# univ_3-2-2-x-rev2.net
KiCad netlist of a schematic drawn in EAGLE
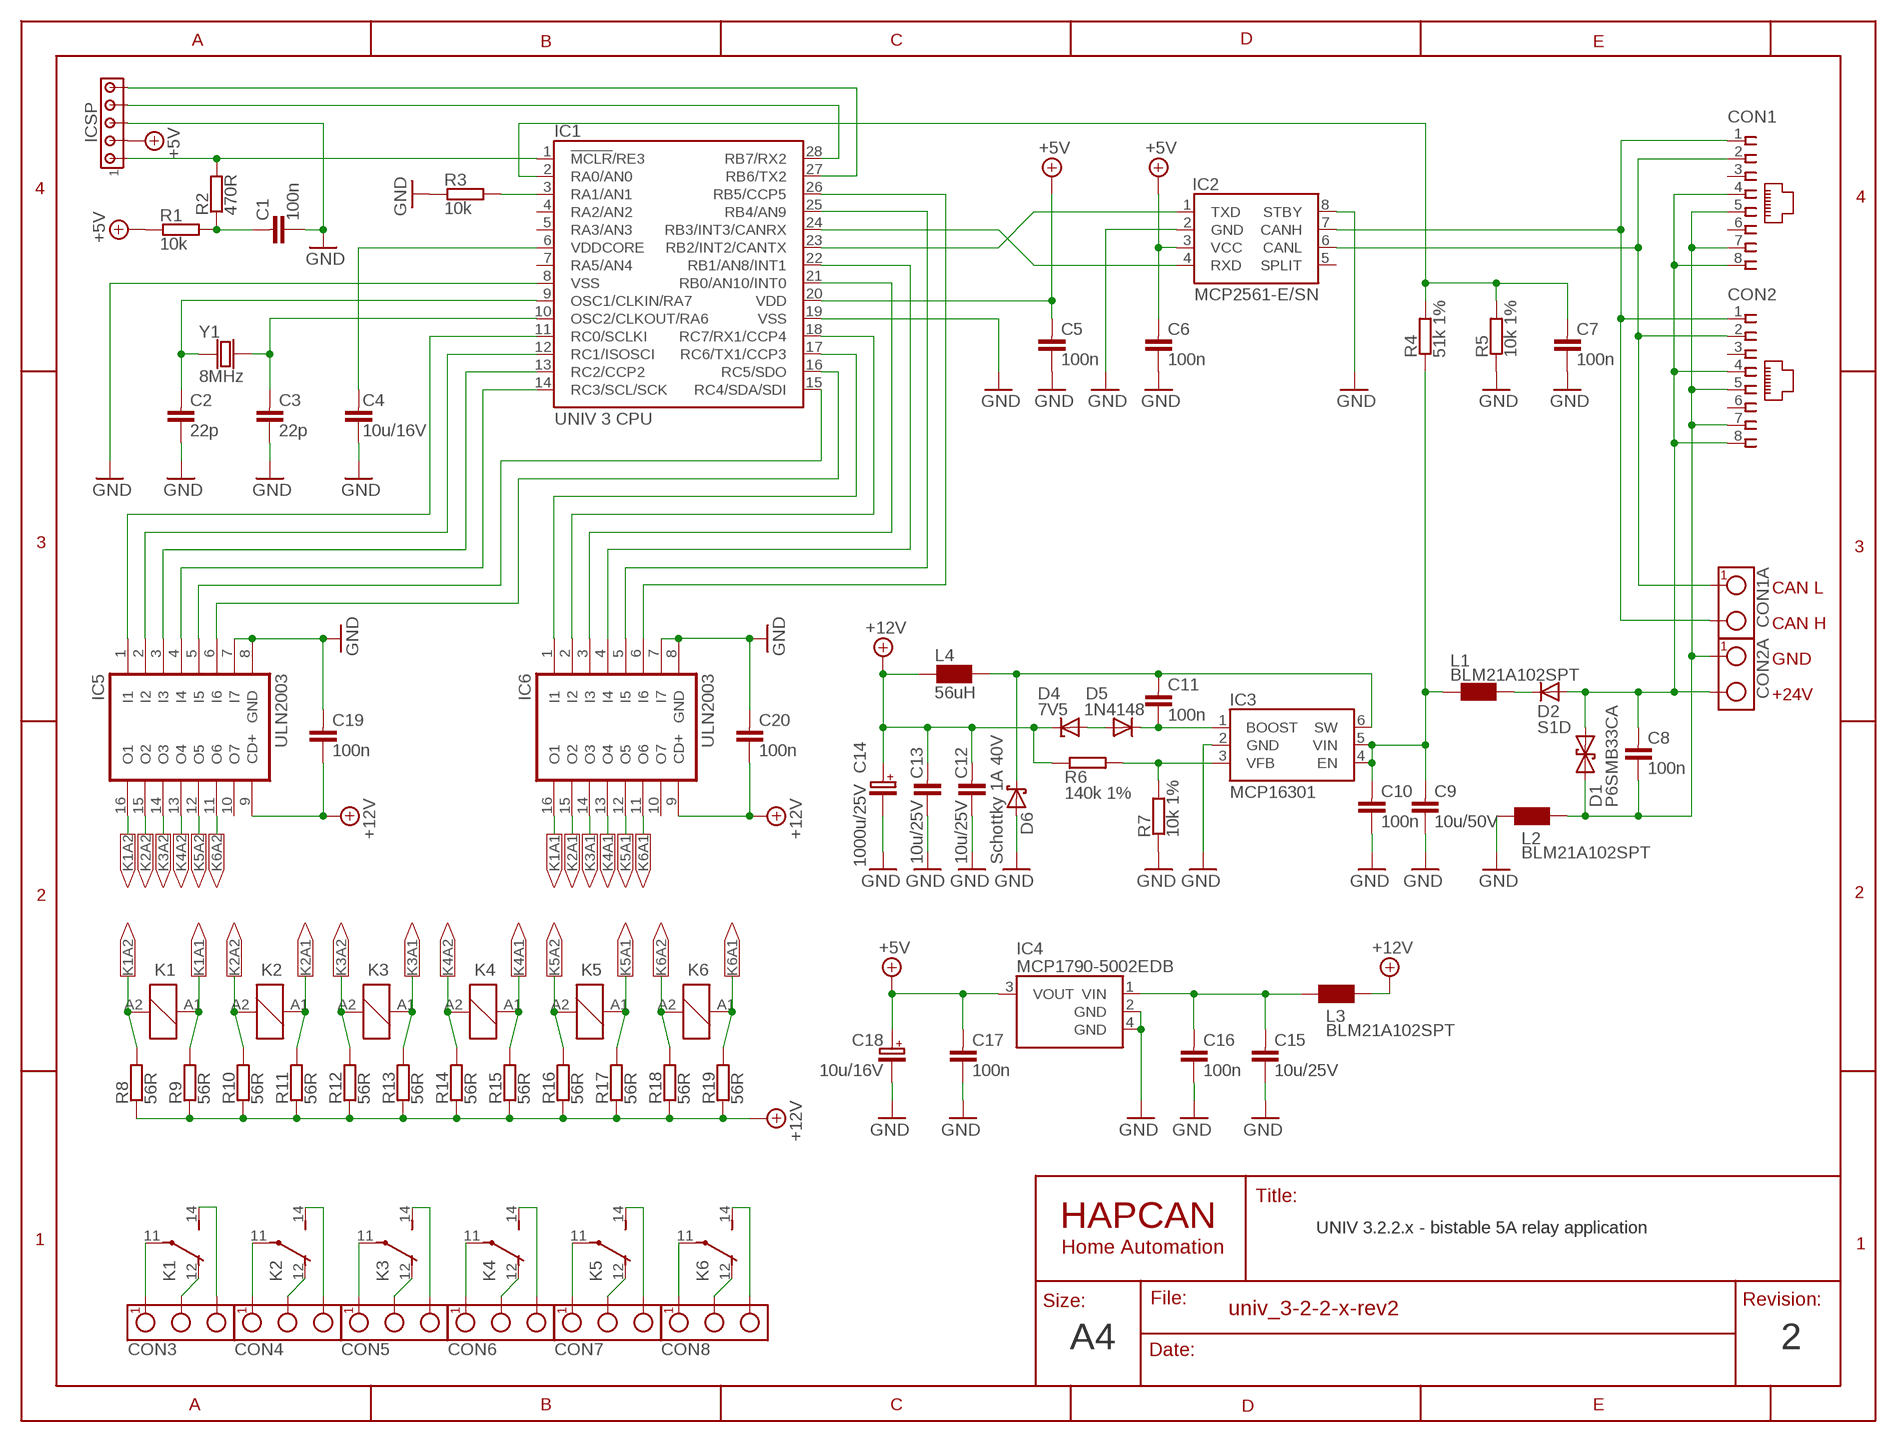
[diagram p0: schematic, sheet 1]

(export (version "E")
  (design (tool "Eeschema 10.0.6"))
  (components
    (comp (ref "C1")
      (value "100n")
      (footprint "eagle-import:0805")
      (libsource (lib "eagle-import") (part "CAPACITOR0805"))
    )
    (comp (ref "C2")
      (value "22p")
      (footprint "eagle-import:0805")
      (libsource (lib "eagle-import") (part "CAPACITOR0805"))
    )
    (comp (ref "C3")
      (value "22p")
      (footprint "eagle-import:0805")
      (libsource (lib "eagle-import") (part "CAPACITOR0805"))
    )
    (comp (ref "C4")
      (value "10u/16V")
      (footprint "eagle-import:0805")
      (libsource (lib "eagle-import") (part "CAPACITOR0805"))
    )
    (comp (ref "C5")
      (value "100n")
      (footprint "eagle-import:0805")
      (libsource (lib "eagle-import") (part "CAPACITOR0805"))
    )
    (comp (ref "C6")
      (value "100n")
      (footprint "eagle-import:0805")
      (libsource (lib "eagle-import") (part "CAPACITOR0805"))
    )
    (comp (ref "C7")
      (value "100n")
      (footprint "eagle-import:0805")
      (libsource (lib "eagle-import") (part "CAPACITOR0805"))
    )
    (comp (ref "C8")
      (value "100n")
      (footprint "eagle-import:0805")
      (libsource (lib "eagle-import") (part "CAPACITOR0805"))
    )
    (comp (ref "C9")
      (value "10u/50V")
      (footprint "eagle-import:1210")
      (libsource (lib "eagle-import") (part "CAPACITOR1210"))
    )
    (comp (ref "C10")
      (value "100n")
      (footprint "eagle-import:0805")
      (libsource (lib "eagle-import") (part "CAPACITOR0805"))
    )
    (comp (ref "C11")
      (value "100n")
      (footprint "eagle-import:0805")
      (libsource (lib "eagle-import") (part "CAPACITOR0805"))
    )
    (comp (ref "C12")
      (value "10u/25V")
      (footprint "eagle-import:1206")
      (libsource (lib "eagle-import") (part "CAPACITOR1206"))
    )
    (comp (ref "C13")
      (value "10u/25V")
      (footprint "eagle-import:1206")
      (libsource (lib "eagle-import") (part "CAPACITOR1206"))
    )
    (comp (ref "C14")
      (value "1000u/25V")
      (footprint "eagle-import:CAP-5X10.5")
      (libsource (lib "eagle-import") (part "CAPACITOR-POLARIZED-5X10.5"))
    )
    (comp (ref "C15")
      (value "10u/25V")
      (footprint "eagle-import:1206")
      (libsource (lib "eagle-import") (part "CAPACITOR1206"))
    )
    (comp (ref "C16")
      (value "100n")
      (footprint "eagle-import:0805")
      (libsource (lib "eagle-import") (part "CAPACITOR0805"))
    )
    (comp (ref "C17")
      (value "100n")
      (footprint "eagle-import:0805")
      (libsource (lib "eagle-import") (part "CAPACITOR0805"))
    )
    (comp (ref "C18")
      (value "10u/16V")
      (footprint "eagle-import:SMC_B")
      (libsource (lib "eagle-import") (part "CAPACITOR-POLARIZED-SMC_B"))
    )
    (comp (ref "C19")
      (value "100n")
      (footprint "eagle-import:0805")
      (libsource (lib "eagle-import") (part "CAPACITOR0805"))
    )
    (comp (ref "C20")
      (value "100n")
      (footprint "eagle-import:0805")
      (libsource (lib "eagle-import") (part "CAPACITOR0805"))
    )
    (comp (ref "CON1")
      (value "RJ45-SOCKET")
      (footprint "eagle-import:RJ45-PCB-SOCKET")
      (libsource (lib "eagle-import") (part "RJ45-SOCKET"))
    )
    (comp (ref "CON1A")
      (value "TERMINAL-2")
      (footprint "eagle-import:ARK2-5X10,5MM")
      (libsource (lib "eagle-import") (part "TERMINAL-2-5X10,5MM"))
    )
    (comp (ref "CON2")
      (value "RJ45-SOCKET")
      (footprint "eagle-import:RJ45-PCB-SOCKET")
      (libsource (lib "eagle-import") (part "RJ45-SOCKET"))
    )
    (comp (ref "CON2A")
      (value "TERMINAL-2")
      (footprint "eagle-import:ARK2-5X10,5MM")
      (libsource (lib "eagle-import") (part "TERMINAL-2-5X10,5MM"))
    )
    (comp (ref "CON3")
      (value "TERMINAL-3-5X10.5MM")
      (footprint "eagle-import:ARK3-5X10.5MM")
      (libsource (lib "eagle-import") (part "TERMINAL-3-5X10.5MM"))
    )
    (comp (ref "CON4")
      (value "TERMINAL-3-5X10.5MM")
      (footprint "eagle-import:ARK3-5X10.5MM")
      (libsource (lib "eagle-import") (part "TERMINAL-3-5X10.5MM"))
    )
    (comp (ref "CON5")
      (value "TERMINAL-3-5X10.5MM")
      (footprint "eagle-import:ARK3-5X10.5MM")
      (libsource (lib "eagle-import") (part "TERMINAL-3-5X10.5MM"))
    )
    (comp (ref "CON6")
      (value "TERMINAL-3-5X10.5MM")
      (footprint "eagle-import:ARK3-5X10.5MM")
      (libsource (lib "eagle-import") (part "TERMINAL-3-5X10.5MM"))
    )
    (comp (ref "CON7")
      (value "TERMINAL-3-5X10.5MM")
      (footprint "eagle-import:ARK3-5X10.5MM")
      (libsource (lib "eagle-import") (part "TERMINAL-3-5X10.5MM"))
    )
    (comp (ref "CON8")
      (value "TERMINAL-3-5X10.5MM")
      (footprint "eagle-import:ARK3-5X10.5MM")
      (libsource (lib "eagle-import") (part "TERMINAL-3-5X10.5MM"))
    )
    (comp (ref "D1")
      (value "P6SMB33CA")
      (footprint "eagle-import:DO-214_TRANSIL2")
      (libsource (lib "eagle-import") (part "DIODE_TRANSIL2"))
    )
    (comp (ref "D2")
      (value "S1D")
      (footprint "eagle-import:DO-214")
      (libsource (lib "eagle-import") (part "DIODE_DO-214"))
    )
    (comp (ref "D4")
      (value "7V5")
      (footprint "eagle-import:SOD-80")
      (libsource (lib "eagle-import") (part "DIODE_ZENER_SOD-80"))
    )
    (comp (ref "D5")
      (value "1N4148")
      (footprint "eagle-import:0805")
      (libsource (lib "eagle-import") (part "DIODE_0805"))
    )
    (comp (ref "D6")
      (value "Schottky 1A 40V")
      (footprint "eagle-import:DO-214")
      (libsource (lib "eagle-import") (part "DIODE_TRANSIL1_DO214"))
    )
    (comp (ref "IC1")
      (value "UNIV 3 CPU")
      (footprint "eagle-import:UNIV3CPU")
      (libsource (lib "eagle-import") (part "UNIV3CPU-I/SO"))
    )
    (comp (ref "IC2")
      (value "MCP2561-E/SN")
      (footprint "eagle-import:SO-08")
      (libsource (lib "eagle-import") (part "MCP2561-E/SN"))
    )
    (comp (ref "IC3")
      (value "MCP16301")
      (footprint "eagle-import:SOT-23-6")
      (libsource (lib "eagle-import") (part "MCP16301SOT23-6"))
    )
    (comp (ref "IC4")
      (value "MCP1790-5002EDB")
      (footprint "eagle-import:SOT-223")
      (libsource (lib "eagle-import") (part "MCP1826SOT223-3"))
    )
    (comp (ref "IC5")
      (value "ULN2003")
      (footprint "eagle-import:SO-16")
      (libsource (lib "eagle-import") (part "ULN2003"))
    )
    (comp (ref "IC6")
      (value "ULN2003")
      (footprint "eagle-import:SO-16")
      (libsource (lib "eagle-import") (part "ULN2003"))
    )
    (comp (ref "ICSP")
      (value "HEADER5")
      (footprint "eagle-import:SIP-5")
      (libsource (lib "eagle-import") (part "HEADER5"))
    )
    (comp (ref "K1")
      (value "RELAY_PE")
      (footprint "eagle-import:RELAY_PE")
      (libsource (lib "eagle-import") (part "RELAY_PE"))
    )
    (comp (ref "K2")
      (value "RELAY_PE")
      (footprint "eagle-import:RELAY_PE")
      (libsource (lib "eagle-import") (part "RELAY_PE"))
    )
    (comp (ref "K3")
      (value "RELAY_PE")
      (footprint "eagle-import:RELAY_PE")
      (libsource (lib "eagle-import") (part "RELAY_PE"))
    )
    (comp (ref "K4")
      (value "RELAY_PE")
      (footprint "eagle-import:RELAY_PE")
      (libsource (lib "eagle-import") (part "RELAY_PE"))
    )
    (comp (ref "K5")
      (value "RELAY_PE")
      (footprint "eagle-import:RELAY_PE")
      (libsource (lib "eagle-import") (part "RELAY_PE"))
    )
    (comp (ref "K6")
      (value "RELAY_PE")
      (footprint "eagle-import:RELAY_PE")
      (libsource (lib "eagle-import") (part "RELAY_PE"))
    )
    (comp (ref "L1")
      (value "BLM21A102SPT")
      (footprint "eagle-import:0805")
      (libsource (lib "eagle-import") (part "CHOKE0805"))
    )
    (comp (ref "L2")
      (value "BLM21A102SPT")
      (footprint "eagle-import:0805")
      (libsource (lib "eagle-import") (part "CHOKE0805"))
    )
    (comp (ref "L3")
      (value "BLM21A102SPT")
      (footprint "eagle-import:0805")
      (libsource (lib "eagle-import") (part "CHOKE0805"))
    )
    (comp (ref "L4")
      (value "56uH")
      (footprint "eagle-import:CHOKE-DER0705")
      (libsource (lib "eagle-import") (part "CHOKEDER0705"))
    )
    (comp (ref "R1")
      (value "10k")
      (footprint "eagle-import:0805")
      (libsource (lib "eagle-import") (part "RESISTOR0805"))
    )
    (comp (ref "R2")
      (value "470R")
      (footprint "eagle-import:0805")
      (libsource (lib "eagle-import") (part "RESISTOR0805"))
    )
    (comp (ref "R3")
      (value "10k")
      (footprint "eagle-import:0805")
      (libsource (lib "eagle-import") (part "RESISTOR0805"))
    )
    (comp (ref "R4")
      (value "51k 1%")
      (footprint "eagle-import:0805")
      (libsource (lib "eagle-import") (part "RESISTOR0805"))
    )
    (comp (ref "R5")
      (value "10k 1%")
      (footprint "eagle-import:0805")
      (libsource (lib "eagle-import") (part "RESISTOR0805"))
    )
    (comp (ref "R6")
      (value "140k 1%")
      (footprint "eagle-import:0805")
      (libsource (lib "eagle-import") (part "RESISTOR0805"))
    )
    (comp (ref "R7")
      (value "10k 1%")
      (footprint "eagle-import:0805")
      (libsource (lib "eagle-import") (part "RESISTOR0805"))
    )
    (comp (ref "R8")
      (value "56R")
      (footprint "eagle-import:1206")
      (libsource (lib "eagle-import") (part "RESISTOR1206"))
    )
    (comp (ref "R9")
      (value "56R")
      (footprint "eagle-import:1206")
      (libsource (lib "eagle-import") (part "RESISTOR1206"))
    )
    (comp (ref "R10")
      (value "56R")
      (footprint "eagle-import:1206")
      (libsource (lib "eagle-import") (part "RESISTOR1206"))
    )
    (comp (ref "R11")
      (value "56R")
      (footprint "eagle-import:1206")
      (libsource (lib "eagle-import") (part "RESISTOR1206"))
    )
    (comp (ref "R12")
      (value "56R")
      (footprint "eagle-import:1206")
      (libsource (lib "eagle-import") (part "RESISTOR1206"))
    )
    (comp (ref "R13")
      (value "56R")
      (footprint "eagle-import:1206")
      (libsource (lib "eagle-import") (part "RESISTOR1206"))
    )
    (comp (ref "R14")
      (value "56R")
      (footprint "eagle-import:1206")
      (libsource (lib "eagle-import") (part "RESISTOR1206"))
    )
    (comp (ref "R15")
      (value "56R")
      (footprint "eagle-import:1206")
      (libsource (lib "eagle-import") (part "RESISTOR1206"))
    )
    (comp (ref "R16")
      (value "56R")
      (footprint "eagle-import:1206")
      (libsource (lib "eagle-import") (part "RESISTOR1206"))
    )
    (comp (ref "R17")
      (value "56R")
      (footprint "eagle-import:1206")
      (libsource (lib "eagle-import") (part "RESISTOR1206"))
    )
    (comp (ref "R18")
      (value "56R")
      (footprint "eagle-import:1206")
      (libsource (lib "eagle-import") (part "RESISTOR1206"))
    )
    (comp (ref "R19")
      (value "56R")
      (footprint "eagle-import:1206")
      (libsource (lib "eagle-import") (part "RESISTOR1206"))
    )
    (comp (ref "Y1")
      (value "8MHz")
      (footprint "eagle-import:CRYSTAL-HC49V")
      (libsource (lib "eagle-import") (part "CRYSTAL-HC49V"))
    )
  )
  (nets
    (net (code "1") (name "+5V") (class "Default")
      (node (ref "C17") (pin "1") (pinfunction "1_1") (pintype "passive"))
      (node (ref "C18") (pin "+") (pinfunction "1_+") (pintype "passive"))
      (node (ref "C5") (pin "1") (pinfunction "1_1") (pintype "passive"))
      (node (ref "C6") (pin "1") (pinfunction "1_1") (pintype "passive"))
      (node (ref "IC1") (pin "20") (pinfunction "VDD_20") (pintype "bidirectional"))
      (node (ref "IC2") (pin "3") (pinfunction "VCC_3") (pintype "bidirectional"))
      (node (ref "IC4") (pin "3") (pinfunction "VOUT_3") (pintype "bidirectional"))
      (node (ref "ICSP") (pin "2") (pinfunction "2_2") (pintype "passive"))
      (node (ref "R1") (pin "1") (pinfunction "1_1") (pintype "passive"))
    )
    (net (code "2") (name "+12V") (class "Default")
      (node (ref "C12") (pin "1") (pinfunction "1_1") (pintype "passive"))
      (node (ref "C13") (pin "1") (pinfunction "1_1") (pintype "passive"))
      (node (ref "C14") (pin "+") (pinfunction "1_+") (pintype "passive"))
      (node (ref "C19") (pin "2") (pinfunction "2_2") (pintype "passive"))
      (node (ref "C20") (pin "2") (pinfunction "2_2") (pintype "passive"))
      (node (ref "D4") (pin "C") (pinfunction "C_C") (pintype "passive"))
      (node (ref "IC5") (pin "9") (pinfunction "CD+_9") (pintype "passive"))
      (node (ref "IC6") (pin "9") (pinfunction "CD+_9") (pintype "passive"))
      (node (ref "L3") (pin "2") (pinfunction "2_2") (pintype "passive"))
      (node (ref "L4") (pin "1") (pinfunction "1_1") (pintype "passive"))
      (node (ref "R10") (pin "1") (pinfunction "1_1") (pintype "passive"))
      (node (ref "R11") (pin "1") (pinfunction "1_1") (pintype "passive"))
      (node (ref "R12") (pin "1") (pinfunction "1_1") (pintype "passive"))
      (node (ref "R13") (pin "1") (pinfunction "1_1") (pintype "passive"))
      (node (ref "R14") (pin "1") (pinfunction "1_1") (pintype "passive"))
      (node (ref "R15") (pin "1") (pinfunction "1_1") (pintype "passive"))
      (node (ref "R16") (pin "1") (pinfunction "1_1") (pintype "passive"))
      (node (ref "R17") (pin "1") (pinfunction "1_1") (pintype "passive"))
      (node (ref "R18") (pin "1") (pinfunction "1_1") (pintype "passive"))
      (node (ref "R19") (pin "1") (pinfunction "1_1") (pintype "passive"))
      (node (ref "R6") (pin "1") (pinfunction "1_1") (pintype "passive"))
      (node (ref "R8") (pin "1") (pinfunction "1_1") (pintype "passive"))
      (node (ref "R9") (pin "1") (pinfunction "1_1") (pintype "passive"))
    )
    (net (code "3") (name "/K1A1") (class "Default")
      (node (ref "IC6") (pin "16") (pinfunction "O1_16") (pintype "open_collector"))
      (node (ref "K1") (pin "A1") (pinfunction "1_A1") (pintype "passive"))
      (node (ref "R9") (pin "2") (pinfunction "2_2") (pintype "passive"))
    )
    (net (code "4") (name "/K1A2") (class "Default")
      (node (ref "IC5") (pin "16") (pinfunction "O1_16") (pintype "open_collector"))
      (node (ref "K1") (pin "A2") (pinfunction "2_A2") (pintype "passive"))
      (node (ref "R8") (pin "2") (pinfunction "2_2") (pintype "passive"))
    )
    (net (code "5") (name "/K2A1") (class "Default")
      (node (ref "IC6") (pin "15") (pinfunction "O2_15") (pintype "open_collector"))
      (node (ref "K2") (pin "A1") (pinfunction "1_A1") (pintype "passive"))
      (node (ref "R11") (pin "2") (pinfunction "2_2") (pintype "passive"))
    )
    (net (code "6") (name "/K2A2") (class "Default")
      (node (ref "IC5") (pin "15") (pinfunction "O2_15") (pintype "open_collector"))
      (node (ref "K2") (pin "A2") (pinfunction "2_A2") (pintype "passive"))
      (node (ref "R10") (pin "2") (pinfunction "2_2") (pintype "passive"))
    )
    (net (code "7") (name "/K3A1") (class "Default")
      (node (ref "IC6") (pin "14") (pinfunction "O3_14") (pintype "open_collector"))
      (node (ref "K3") (pin "A1") (pinfunction "1_A1") (pintype "passive"))
      (node (ref "R13") (pin "2") (pinfunction "2_2") (pintype "passive"))
    )
    (net (code "8") (name "/K3A2") (class "Default")
      (node (ref "IC5") (pin "14") (pinfunction "O3_14") (pintype "open_collector"))
      (node (ref "K3") (pin "A2") (pinfunction "2_A2") (pintype "passive"))
      (node (ref "R12") (pin "2") (pinfunction "2_2") (pintype "passive"))
    )
    (net (code "9") (name "/K4A1") (class "Default")
      (node (ref "IC6") (pin "13") (pinfunction "O4_13") (pintype "open_collector"))
      (node (ref "K4") (pin "A1") (pinfunction "1_A1") (pintype "passive"))
      (node (ref "R15") (pin "2") (pinfunction "2_2") (pintype "passive"))
    )
    (net (code "10") (name "/K4A2") (class "Default")
      (node (ref "IC5") (pin "13") (pinfunction "O4_13") (pintype "open_collector"))
      (node (ref "K4") (pin "A2") (pinfunction "2_A2") (pintype "passive"))
      (node (ref "R14") (pin "2") (pinfunction "2_2") (pintype "passive"))
    )
    (net (code "11") (name "/K5A1") (class "Default")
      (node (ref "IC6") (pin "12") (pinfunction "O5_12") (pintype "open_collector"))
      (node (ref "K5") (pin "A1") (pinfunction "1_A1") (pintype "passive"))
      (node (ref "R17") (pin "2") (pinfunction "2_2") (pintype "passive"))
    )
    (net (code "12") (name "/K5A2") (class "Default")
      (node (ref "IC5") (pin "12") (pinfunction "O5_12") (pintype "open_collector"))
      (node (ref "K5") (pin "A2") (pinfunction "2_A2") (pintype "passive"))
      (node (ref "R16") (pin "2") (pinfunction "2_2") (pintype "passive"))
    )
    (net (code "13") (name "/K6A1") (class "Default")
      (node (ref "IC6") (pin "11") (pinfunction "O6_11") (pintype "open_collector"))
      (node (ref "K6") (pin "A1") (pinfunction "1_A1") (pintype "passive"))
      (node (ref "R19") (pin "2") (pinfunction "2_2") (pintype "passive"))
    )
    (net (code "14") (name "/K6A2") (class "Default")
      (node (ref "IC5") (pin "11") (pinfunction "O6_11") (pintype "open_collector"))
      (node (ref "K6") (pin "A2") (pinfunction "2_A2") (pintype "passive"))
      (node (ref "R18") (pin "2") (pinfunction "2_2") (pintype "passive"))
    )
    (net (code "15") (name "GND") (class "Default")
      (node (ref "C1") (pin "2") (pinfunction "2_2") (pintype "passive"))
      (node (ref "C10") (pin "2") (pinfunction "2_2") (pintype "passive"))
      (node (ref "C12") (pin "2") (pinfunction "2_2") (pintype "passive"))
      (node (ref "C13") (pin "2") (pinfunction "2_2") (pintype "passive"))
      (node (ref "C14") (pin "-") (pinfunction "2_-") (pintype "passive"))
      (node (ref "C15") (pin "2") (pinfunction "2_2") (pintype "passive"))
      (node (ref "C16") (pin "2") (pinfunction "2_2") (pintype "passive"))
      (node (ref "C17") (pin "2") (pinfunction "2_2") (pintype "passive"))
      (node (ref "C18") (pin "-") (pinfunction "2_-") (pintype "passive"))
      (node (ref "C19") (pin "1") (pinfunction "1_1") (pintype "passive"))
      (node (ref "C2") (pin "2") (pinfunction "2_2") (pintype "passive"))
      (node (ref "C20") (pin "1") (pinfunction "1_1") (pintype "passive"))
      (node (ref "C3") (pin "2") (pinfunction "2_2") (pintype "passive"))
      (node (ref "C4") (pin "2") (pinfunction "2_2") (pintype "passive"))
      (node (ref "C5") (pin "2") (pinfunction "2_2") (pintype "passive"))
      (node (ref "C6") (pin "2") (pinfunction "2_2") (pintype "passive"))
      (node (ref "C7") (pin "2") (pinfunction "2_2") (pintype "passive"))
      (node (ref "C9") (pin "2") (pinfunction "2_2") (pintype "passive"))
      (node (ref "D6") (pin "A") (pinfunction "A_A") (pintype "passive"))
      (node (ref "IC1") (pin "19") (pinfunction "VSS_19") (pintype "bidirectional"))
      (node (ref "IC1") (pin "8") (pinfunction "VSS_8") (pintype "bidirectional"))
      (node (ref "IC2") (pin "2") (pinfunction "GND_2") (pintype "bidirectional"))
      (node (ref "IC2") (pin "8") (pinfunction "STBY_8") (pintype "bidirectional"))
      (node (ref "IC3") (pin "2") (pinfunction "GND_2") (pintype "bidirectional"))
      (node (ref "IC4") (pin "2") (pinfunction "GND_2") (pintype "bidirectional"))
      (node (ref "IC4") (pin "4") (pinfunction "GND_4") (pintype "bidirectional"))
      (node (ref "IC5") (pin "7") (pinfunction "I7_7") (pintype "input"))
      (node (ref "IC5") (pin "8") (pinfunction "GND_8") (pintype "power_in"))
      (node (ref "IC6") (pin "7") (pinfunction "I7_7") (pintype "input"))
      (node (ref "IC6") (pin "8") (pinfunction "GND_8") (pintype "power_in"))
      (node (ref "ICSP") (pin "3") (pinfunction "3_3") (pintype "passive"))
      (node (ref "L2") (pin "1") (pinfunction "1_1") (pintype "passive"))
      (node (ref "R3") (pin "1") (pinfunction "1_1") (pintype "passive"))
      (node (ref "R5") (pin "1") (pinfunction "1_1") (pintype "passive"))
      (node (ref "R7") (pin "1") (pinfunction "1_1") (pintype "passive"))
    )
    (net (code "16") (name "Net-(C1-Pad1)") (class "Default")
      (node (ref "C1") (pin "1") (pinfunction "1_1") (pintype "passive"))
      (node (ref "R1") (pin "2") (pinfunction "2_2") (pintype "passive"))
      (node (ref "R2") (pin "1") (pinfunction "1_1") (pintype "passive"))
    )
    (net (code "17") (name "Net-(D1-1)") (class "Default")
      (node (ref "C8") (pin "2") (pinfunction "2_2") (pintype "passive"))
      (node (ref "CON1") (pin "5") (pinfunction "5_5") (pintype "passive"))
      (node (ref "CON1") (pin "7") (pinfunction "7_7") (pintype "passive"))
      (node (ref "CON2") (pin "5") (pinfunction "5_5") (pintype "passive"))
      (node (ref "CON2") (pin "7") (pinfunction "7_7") (pintype "passive"))
      (node (ref "CON2A") (pin "1") (pinfunction "1_1") (pintype "passive"))
      (node (ref "D1") (pin "A") (pinfunction "1_A") (pintype "passive"))
      (node (ref "L2") (pin "2") (pinfunction "2_2") (pintype "passive"))
    )
    (net (code "18") (name "Net-(D1-2)") (class "Default")
      (node (ref "C8") (pin "1") (pinfunction "1_1") (pintype "passive"))
      (node (ref "CON1") (pin "4") (pinfunction "4_4") (pintype "passive"))
      (node (ref "CON1") (pin "8") (pinfunction "8_8") (pintype "passive"))
      (node (ref "CON2") (pin "4") (pinfunction "4_4") (pintype "passive"))
      (node (ref "CON2") (pin "8") (pinfunction "8_8") (pintype "passive"))
      (node (ref "CON2A") (pin "2") (pinfunction "2_2") (pintype "passive"))
      (node (ref "D1") (pin "C") (pinfunction "2_C") (pintype "passive"))
      (node (ref "D2") (pin "A") (pinfunction "A_A") (pintype "passive"))
    )
    (net (code "19") (name "Net-(D2-PadC)") (class "Default")
      (node (ref "D2") (pin "C") (pinfunction "C_C") (pintype "passive"))
      (node (ref "L1") (pin "2") (pinfunction "2_2") (pintype "passive"))
    )
    (net (code "20") (name "Net-(D5-A)") (class "Default")
      (node (ref "D4") (pin "A") (pinfunction "A_A") (pintype "passive"))
      (node (ref "D5") (pin "2") (pinfunction "A_2") (pintype "passive"))
    )
    (net (code "21") (name "Net-(D5-C)") (class "Default")
      (node (ref "C11") (pin "2") (pinfunction "2_2") (pintype "passive"))
      (node (ref "D5") (pin "1") (pinfunction "C_1") (pintype "passive"))
      (node (ref "IC3") (pin "1") (pinfunction "BOOST_1") (pintype "bidirectional"))
    )
    (net (code "22") (name "Net-(IC1-OSC1{slash}CLKIN{slash}RA7)") (class "Default")
      (node (ref "C2") (pin "1") (pinfunction "1_1") (pintype "passive"))
      (node (ref "IC1") (pin "9") (pinfunction "OSC1/CLKIN/RA7_9") (pintype "bidirectional"))
      (node (ref "Y1") (pin "1") (pinfunction "1_1") (pintype "passive"))
    )
    (net (code "23") (name "Net-(IC1-OSC2{slash}CLKOUT{slash}RA6)") (class "Default")
      (node (ref "C3") (pin "1") (pinfunction "1_1") (pintype "passive"))
      (node (ref "IC1") (pin "10") (pinfunction "OSC2/CLKOUT/RA6_10") (pintype "bidirectional"))
      (node (ref "Y1") (pin "2") (pinfunction "2_2") (pintype "passive"))
    )
    (net (code "24") (name "Net-(IC1-RA0{slash}AN0)") (class "Default")
      (node (ref "C7") (pin "1") (pinfunction "1_1") (pintype "passive"))
      (node (ref "IC1") (pin "2") (pinfunction "RA0/AN0_2") (pintype "bidirectional"))
      (node (ref "R4") (pin "2") (pinfunction "2_2") (pintype "passive"))
      (node (ref "R5") (pin "2") (pinfunction "2_2") (pintype "passive"))
    )
    (net (code "25") (name "Net-(IC1-RA1{slash}AN1)") (class "Default")
      (node (ref "IC1") (pin "3") (pinfunction "RA1/AN1_3") (pintype "bidirectional"))
      (node (ref "R3") (pin "2") (pinfunction "2_2") (pintype "passive"))
    )
    (net (code "26") (name "Net-(IC1-RB0{slash}AN10{slash}INT0)") (class "Default")
      (node (ref "IC1") (pin "21") (pinfunction "RB0/AN10/INT0_21") (pintype "bidirectional"))
      (node (ref "IC6") (pin "3") (pinfunction "I3_3") (pintype "input"))
    )
    (net (code "27") (name "Net-(IC1-RB1{slash}AN8{slash}INT1)") (class "Default")
      (node (ref "IC1") (pin "22") (pinfunction "RB1/AN8/INT1_22") (pintype "bidirectional"))
      (node (ref "IC6") (pin "4") (pinfunction "I4_4") (pintype "input"))
    )
    (net (code "28") (name "Net-(IC1-RB2{slash}INT2{slash}CANTX)") (class "Default")
      (node (ref "IC1") (pin "23") (pinfunction "RB2/INT2/CANTX_23") (pintype "bidirectional"))
      (node (ref "IC2") (pin "1") (pinfunction "TXD_1") (pintype "bidirectional"))
    )
    (net (code "29") (name "Net-(IC1-RB3{slash}INT3{slash}CANRX)") (class "Default")
      (node (ref "IC1") (pin "24") (pinfunction "RB3/INT3/CANRX_24") (pintype "bidirectional"))
      (node (ref "IC2") (pin "4") (pinfunction "RXD_4") (pintype "bidirectional"))
    )
    (net (code "30") (name "Net-(IC1-RB4{slash}AN9)") (class "Default")
      (node (ref "IC1") (pin "25") (pinfunction "RB4/AN9_25") (pintype "bidirectional"))
      (node (ref "IC6") (pin "5") (pinfunction "I5_5") (pintype "input"))
    )
    (net (code "31") (name "Net-(IC1-RB5{slash}CCP5)") (class "Default")
      (node (ref "IC1") (pin "26") (pinfunction "RB5/CCP5_26") (pintype "bidirectional"))
      (node (ref "IC6") (pin "6") (pinfunction "I6_6") (pintype "input"))
    )
    (net (code "32") (name "Net-(IC1-RB6{slash}TX2)") (class "Default")
      (node (ref "IC1") (pin "27") (pinfunction "RB6/TX2_27") (pintype "bidirectional"))
      (node (ref "ICSP") (pin "5") (pinfunction "5_5") (pintype "passive"))
    )
    (net (code "33") (name "Net-(IC1-RB7{slash}RX2)") (class "Default")
      (node (ref "IC1") (pin "28") (pinfunction "RB7/RX2_28") (pintype "bidirectional"))
      (node (ref "ICSP") (pin "4") (pinfunction "4_4") (pintype "passive"))
    )
    (net (code "34") (name "Net-(IC1-RC0{slash}SCLKI)") (class "Default")
      (node (ref "IC1") (pin "11") (pinfunction "RC0/SCLKI_11") (pintype "bidirectional"))
      (node (ref "IC5") (pin "1") (pinfunction "I1_1") (pintype "input"))
    )
    (net (code "35") (name "Net-(IC1-RC1{slash}ISOSCI)") (class "Default")
      (node (ref "IC1") (pin "12") (pinfunction "RC1/ISOSCI_12") (pintype "bidirectional"))
      (node (ref "IC5") (pin "2") (pinfunction "I2_2") (pintype "input"))
    )
    (net (code "36") (name "Net-(IC1-RC2{slash}CCP2)") (class "Default")
      (node (ref "IC1") (pin "13") (pinfunction "RC2/CCP2_13") (pintype "bidirectional"))
      (node (ref "IC5") (pin "3") (pinfunction "I3_3") (pintype "input"))
    )
    (net (code "37") (name "Net-(IC1-RC3{slash}SCL{slash}SCK)") (class "Default")
      (node (ref "IC1") (pin "14") (pinfunction "RC3/SCL/SCK_14") (pintype "bidirectional"))
      (node (ref "IC5") (pin "4") (pinfunction "I4_4") (pintype "input"))
    )
    (net (code "38") (name "Net-(IC1-RC4{slash}SDA{slash}SDI)") (class "Default")
      (node (ref "IC1") (pin "15") (pinfunction "RC4/SDA/SDI_15") (pintype "bidirectional"))
      (node (ref "IC5") (pin "5") (pinfunction "I5_5") (pintype "input"))
    )
    (net (code "39") (name "Net-(IC1-RC5{slash}SDO)") (class "Default")
      (node (ref "IC1") (pin "16") (pinfunction "RC5/SDO_16") (pintype "bidirectional"))
      (node (ref "IC5") (pin "6") (pinfunction "I6_6") (pintype "input"))
    )
    (net (code "40") (name "Net-(IC1-RC6{slash}TX1{slash}CCP3)") (class "Default")
      (node (ref "IC1") (pin "17") (pinfunction "RC6/TX1/CCP3_17") (pintype "bidirectional"))
      (node (ref "IC6") (pin "1") (pinfunction "I1_1") (pintype "input"))
    )
    (net (code "41") (name "Net-(IC1-RC7{slash}RX1{slash}CCP4)") (class "Default")
      (node (ref "IC1") (pin "18") (pinfunction "RC7/RX1/CCP4_18") (pintype "bidirectional"))
      (node (ref "IC6") (pin "2") (pinfunction "I2_2") (pintype "input"))
    )
    (net (code "42") (name "Net-(IC1-VDDCORE)") (class "Default")
      (node (ref "C4") (pin "1") (pinfunction "1_1") (pintype "passive"))
      (node (ref "IC1") (pin "6") (pinfunction "VDDCORE_6") (pintype "bidirectional"))
    )
    (net (code "43") (name "Net-(IC1-~{MCLR}{slash}RE3)") (class "Default")
      (node (ref "IC1") (pin "1") (pinfunction "~{MCLR}/RE3_1") (pintype "bidirectional"))
      (node (ref "ICSP") (pin "1") (pinfunction "1_1") (pintype "passive"))
      (node (ref "R2") (pin "2") (pinfunction "2_2") (pintype "passive"))
    )
    (net (code "44") (name "Net-(IC2-CANH)") (class "Default")
      (node (ref "CON1") (pin "1") (pinfunction "1_1") (pintype "passive"))
      (node (ref "CON1A") (pin "2") (pinfunction "2_2") (pintype "passive"))
      (node (ref "CON2") (pin "1") (pinfunction "1_1") (pintype "passive"))
      (node (ref "IC2") (pin "7") (pinfunction "CANH_7") (pintype "bidirectional"))
    )
    (net (code "45") (name "Net-(IC2-CANL)") (class "Default")
      (node (ref "CON1") (pin "2") (pinfunction "2_2") (pintype "passive"))
      (node (ref "CON1A") (pin "1") (pinfunction "1_1") (pintype "passive"))
      (node (ref "CON2") (pin "2") (pinfunction "2_2") (pintype "passive"))
      (node (ref "IC2") (pin "6") (pinfunction "CANL_6") (pintype "bidirectional"))
    )
    (net (code "46") (name "Net-(IC3-EN)") (class "Default")
      (node (ref "C10") (pin "1") (pinfunction "1_1") (pintype "passive"))
      (node (ref "C9") (pin "1") (pinfunction "1_1") (pintype "passive"))
      (node (ref "IC3") (pin "4") (pinfunction "EN_4") (pintype "bidirectional"))
      (node (ref "IC3") (pin "5") (pinfunction "VIN_5") (pintype "bidirectional"))
      (node (ref "L1") (pin "1") (pinfunction "1_1") (pintype "passive"))
      (node (ref "R4") (pin "1") (pinfunction "1_1") (pintype "passive"))
    )
    (net (code "47") (name "Net-(IC3-SW)") (class "Default")
      (node (ref "C11") (pin "1") (pinfunction "1_1") (pintype "passive"))
      (node (ref "D6") (pin "C") (pinfunction "C_C") (pintype "passive"))
      (node (ref "IC3") (pin "6") (pinfunction "SW_6") (pintype "bidirectional"))
      (node (ref "L4") (pin "2") (pinfunction "2_2") (pintype "passive"))
    )
    (net (code "48") (name "Net-(IC3-VFB)") (class "Default")
      (node (ref "IC3") (pin "3") (pinfunction "VFB_3") (pintype "bidirectional"))
      (node (ref "R6") (pin "2") (pinfunction "2_2") (pintype "passive"))
      (node (ref "R7") (pin "2") (pinfunction "2_2") (pintype "passive"))
    )
    (net (code "49") (name "Net-(IC4-VIN)") (class "Default")
      (node (ref "C15") (pin "1") (pinfunction "1_1") (pintype "passive"))
      (node (ref "C16") (pin "1") (pinfunction "1_1") (pintype "passive"))
      (node (ref "IC4") (pin "1") (pinfunction "VIN_1") (pintype "bidirectional"))
      (node (ref "L3") (pin "1") (pinfunction "1_1") (pintype "passive"))
    )
    (net (code "50") (name "Net-(K1B-COM)") (class "Default")
      (node (ref "CON3") (pin "1") (pinfunction "1_1") (pintype "passive"))
      (node (ref "K1") (pin "11") (pinfunction "COM_11") (pintype "passive"))
    )
    (net (code "51") (name "Net-(K1B-NC)") (class "Default")
      (node (ref "CON3") (pin "2") (pinfunction "2_2") (pintype "passive"))
      (node (ref "K1") (pin "12") (pinfunction "NC_12") (pintype "passive"))
    )
    (net (code "52") (name "Net-(K1B-NO)") (class "Default")
      (node (ref "CON3") (pin "3") (pinfunction "3_3") (pintype "passive"))
      (node (ref "K1") (pin "14") (pinfunction "NO_14") (pintype "passive"))
    )
    (net (code "53") (name "Net-(K2B-COM)") (class "Default")
      (node (ref "CON4") (pin "1") (pinfunction "1_1") (pintype "passive"))
      (node (ref "K2") (pin "11") (pinfunction "COM_11") (pintype "passive"))
    )
    (net (code "54") (name "Net-(K2B-NC)") (class "Default")
      (node (ref "CON4") (pin "2") (pinfunction "2_2") (pintype "passive"))
      (node (ref "K2") (pin "12") (pinfunction "NC_12") (pintype "passive"))
    )
    (net (code "55") (name "Net-(K2B-NO)") (class "Default")
      (node (ref "CON4") (pin "3") (pinfunction "3_3") (pintype "passive"))
      (node (ref "K2") (pin "14") (pinfunction "NO_14") (pintype "passive"))
    )
    (net (code "56") (name "Net-(K3B-COM)") (class "Default")
      (node (ref "CON5") (pin "1") (pinfunction "1_1") (pintype "passive"))
      (node (ref "K3") (pin "11") (pinfunction "COM_11") (pintype "passive"))
    )
    (net (code "57") (name "Net-(K3B-NC)") (class "Default")
      (node (ref "CON5") (pin "2") (pinfunction "2_2") (pintype "passive"))
      (node (ref "K3") (pin "12") (pinfunction "NC_12") (pintype "passive"))
    )
    (net (code "58") (name "Net-(K3B-NO)") (class "Default")
      (node (ref "CON5") (pin "3") (pinfunction "3_3") (pintype "passive"))
      (node (ref "K3") (pin "14") (pinfunction "NO_14") (pintype "passive"))
    )
    (net (code "59") (name "Net-(K4B-COM)") (class "Default")
      (node (ref "CON6") (pin "1") (pinfunction "1_1") (pintype "passive"))
      (node (ref "K4") (pin "11") (pinfunction "COM_11") (pintype "passive"))
    )
    (net (code "60") (name "Net-(K4B-NC)") (class "Default")
      (node (ref "CON6") (pin "2") (pinfunction "2_2") (pintype "passive"))
      (node (ref "K4") (pin "12") (pinfunction "NC_12") (pintype "passive"))
    )
    (net (code "61") (name "Net-(K4B-NO)") (class "Default")
      (node (ref "CON6") (pin "3") (pinfunction "3_3") (pintype "passive"))
      (node (ref "K4") (pin "14") (pinfunction "NO_14") (pintype "passive"))
    )
    (net (code "62") (name "Net-(K5B-COM)") (class "Default")
      (node (ref "CON7") (pin "1") (pinfunction "1_1") (pintype "passive"))
      (node (ref "K5") (pin "11") (pinfunction "COM_11") (pintype "passive"))
    )
    (net (code "63") (name "Net-(K5B-NC)") (class "Default")
      (node (ref "CON7") (pin "2") (pinfunction "2_2") (pintype "passive"))
      (node (ref "K5") (pin "12") (pinfunction "NC_12") (pintype "passive"))
    )
    (net (code "64") (name "Net-(K5B-NO)") (class "Default")
      (node (ref "CON7") (pin "3") (pinfunction "3_3") (pintype "passive"))
      (node (ref "K5") (pin "14") (pinfunction "NO_14") (pintype "passive"))
    )
    (net (code "65") (name "Net-(K6B-COM)") (class "Default")
      (node (ref "CON8") (pin "1") (pinfunction "1_1") (pintype "passive"))
      (node (ref "K6") (pin "11") (pinfunction "COM_11") (pintype "passive"))
    )
    (net (code "66") (name "Net-(K6B-NC)") (class "Default")
      (node (ref "CON8") (pin "2") (pinfunction "2_2") (pintype "passive"))
      (node (ref "K6") (pin "12") (pinfunction "NC_12") (pintype "passive"))
    )
    (net (code "67") (name "Net-(K6B-NO)") (class "Default")
      (node (ref "CON8") (pin "3") (pinfunction "3_3") (pintype "passive"))
      (node (ref "K6") (pin "14") (pinfunction "NO_14") (pintype "passive"))
    )
    (net (code "68") (name "unconnected-(CON1-Pad3)") (class "Default")
      (node (ref "CON1") (pin "3") (pinfunction "3_3") (pintype "passive"))
    )
    (net (code "69") (name "unconnected-(CON1-Pad6)") (class "Default")
      (node (ref "CON1") (pin "6") (pinfunction "6_6") (pintype "passive"))
    )
    (net (code "70") (name "unconnected-(CON2-Pad3)") (class "Default")
      (node (ref "CON2") (pin "3") (pinfunction "3_3") (pintype "passive"))
    )
    (net (code "71") (name "unconnected-(CON2-Pad6)") (class "Default")
      (node (ref "CON2") (pin "6") (pinfunction "6_6") (pintype "passive"))
    )
    (net (code "72") (name "unconnected-(IC1-RA2{slash}AN2-Pad4)") (class "Default")
      (node (ref "IC1") (pin "4") (pinfunction "RA2/AN2_4") (pintype "bidirectional"))
    )
    (net (code "73") (name "unconnected-(IC1-RA3{slash}AN3-Pad5)") (class "Default")
      (node (ref "IC1") (pin "5") (pinfunction "RA3/AN3_5") (pintype "bidirectional"))
    )
    (net (code "74") (name "unconnected-(IC1-RA5{slash}AN4-Pad7)") (class "Default")
      (node (ref "IC1") (pin "7") (pinfunction "RA5/AN4_7") (pintype "bidirectional"))
    )
    (net (code "75") (name "unconnected-(IC2-SPLIT-Pad5)") (class "Default")
      (node (ref "IC2") (pin "5") (pinfunction "SPLIT_5") (pintype "bidirectional"))
    )
    (net (code "76") (name "unconnected-(IC5-O7-Pad10)") (class "Default")
      (node (ref "IC5") (pin "10") (pinfunction "O7_10") (pintype "open_collector"))
    )
    (net (code "77") (name "unconnected-(IC6-O7-Pad10)") (class "Default")
      (node (ref "IC6") (pin "10") (pinfunction "O7_10") (pintype "open_collector"))
    )
  )
)
